# input-breakout.net
KiCad netlist of a schematic drawn in EAGLE
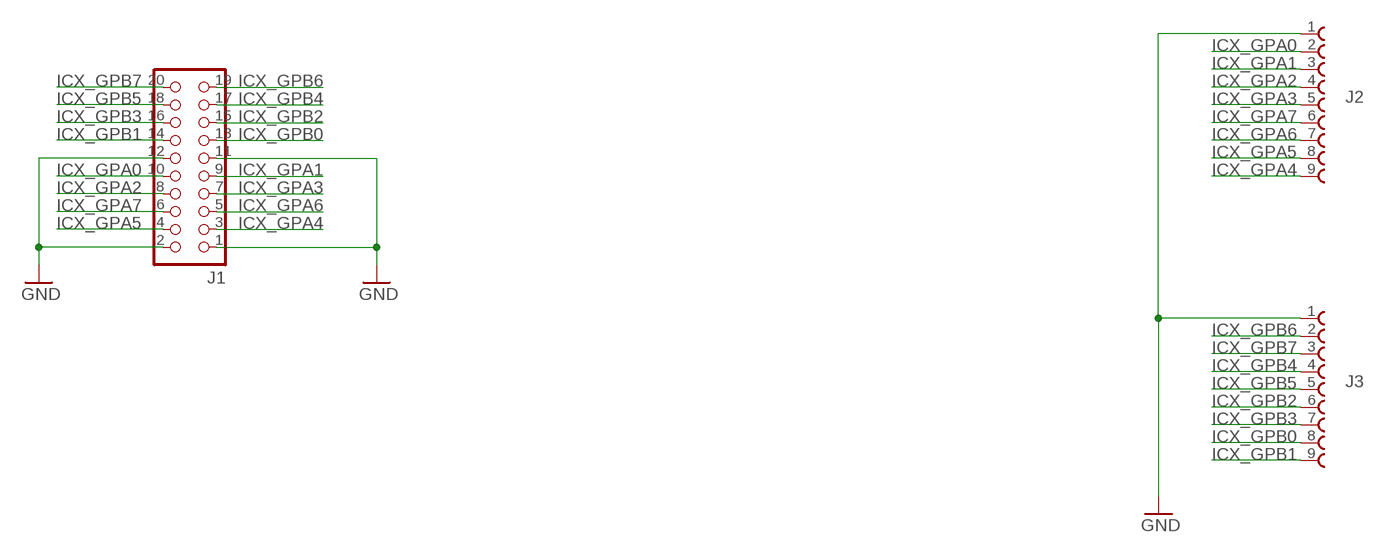
[diagram p0: schematic, sheet 1]

(export (version "E")
  (design (tool "Eeschema 10.0.6"))
  (components
    (comp (ref "J1")
      (value "CON_HEADER_2X10-SHROUDED")
      (footprint "eagle-import:PINSHRD_PTH_2X10")
      (libsource (lib "eagle-import") (part "CON_HEADER_2X10-SHROUDED"))
    )
    (comp (ref "J2")
      (value "69132211000_XX")
      (footprint "eagle-import:69132211000_XX")
      (libsource (lib "eagle-import") (part "69132211000_XX"))
    )
    (comp (ref "J3")
      (value "69132211000_XX")
      (footprint "eagle-import:69132211000_XX")
      (libsource (lib "eagle-import") (part "69132211000_XX"))
    )
  )
  (nets
    (net (code "1") (name "/ICX_GPA0") (class "Default")
      (node (ref "J1") (pin "10") (pinfunction "10_10") (pintype "passive"))
      (node (ref "J2") (pin "2") (pinfunction "2_2") (pintype "passive"))
    )
    (net (code "2") (name "/ICX_GPA1") (class "Default")
      (node (ref "J1") (pin "9") (pinfunction "9_9") (pintype "passive"))
      (node (ref "J2") (pin "3") (pinfunction "3_3") (pintype "passive"))
    )
    (net (code "3") (name "/ICX_GPA2") (class "Default")
      (node (ref "J1") (pin "8") (pinfunction "8_8") (pintype "passive"))
      (node (ref "J2") (pin "4") (pinfunction "4_4") (pintype "passive"))
    )
    (net (code "4") (name "/ICX_GPA3") (class "Default")
      (node (ref "J1") (pin "7") (pinfunction "7_7") (pintype "passive"))
      (node (ref "J2") (pin "5") (pinfunction "5_5") (pintype "passive"))
    )
    (net (code "5") (name "/ICX_GPA4") (class "Default")
      (node (ref "J1") (pin "3") (pinfunction "3_3") (pintype "passive"))
      (node (ref "J2") (pin "9") (pinfunction "9_9") (pintype "passive"))
    )
    (net (code "6") (name "/ICX_GPA5") (class "Default")
      (node (ref "J1") (pin "4") (pinfunction "4_4") (pintype "passive"))
      (node (ref "J2") (pin "8") (pinfunction "8_8") (pintype "passive"))
    )
    (net (code "7") (name "/ICX_GPA6") (class "Default")
      (node (ref "J1") (pin "5") (pinfunction "5_5") (pintype "passive"))
      (node (ref "J2") (pin "7") (pinfunction "7_7") (pintype "passive"))
    )
    (net (code "8") (name "/ICX_GPA7") (class "Default")
      (node (ref "J1") (pin "6") (pinfunction "6_6") (pintype "passive"))
      (node (ref "J2") (pin "6") (pinfunction "6_6") (pintype "passive"))
    )
    (net (code "9") (name "/ICX_GPB0") (class "Default")
      (node (ref "J1") (pin "13") (pinfunction "13_13") (pintype "passive"))
      (node (ref "J3") (pin "8") (pinfunction "8_8") (pintype "passive"))
    )
    (net (code "10") (name "/ICX_GPB1") (class "Default")
      (node (ref "J1") (pin "14") (pinfunction "14_14") (pintype "passive"))
      (node (ref "J3") (pin "9") (pinfunction "9_9") (pintype "passive"))
    )
    (net (code "11") (name "/ICX_GPB2") (class "Default")
      (node (ref "J1") (pin "15") (pinfunction "15_15") (pintype "passive"))
      (node (ref "J3") (pin "6") (pinfunction "6_6") (pintype "passive"))
    )
    (net (code "12") (name "/ICX_GPB3") (class "Default")
      (node (ref "J1") (pin "16") (pinfunction "16_16") (pintype "passive"))
      (node (ref "J3") (pin "7") (pinfunction "7_7") (pintype "passive"))
    )
    (net (code "13") (name "/ICX_GPB4") (class "Default")
      (node (ref "J1") (pin "17") (pinfunction "17_17") (pintype "passive"))
      (node (ref "J3") (pin "4") (pinfunction "4_4") (pintype "passive"))
    )
    (net (code "14") (name "/ICX_GPB5") (class "Default")
      (node (ref "J1") (pin "18") (pinfunction "18_18") (pintype "passive"))
      (node (ref "J3") (pin "5") (pinfunction "5_5") (pintype "passive"))
    )
    (net (code "15") (name "/ICX_GPB6") (class "Default")
      (node (ref "J1") (pin "19") (pinfunction "19_19") (pintype "passive"))
      (node (ref "J3") (pin "2") (pinfunction "2_2") (pintype "passive"))
    )
    (net (code "16") (name "/ICX_GPB7") (class "Default")
      (node (ref "J1") (pin "20") (pinfunction "20_20") (pintype "passive"))
      (node (ref "J3") (pin "3") (pinfunction "3_3") (pintype "passive"))
    )
    (net (code "17") (name "GND") (class "Default")
      (node (ref "J1") (pin "1") (pinfunction "1_1") (pintype "passive"))
      (node (ref "J1") (pin "11") (pinfunction "11_11") (pintype "passive"))
      (node (ref "J1") (pin "12") (pinfunction "12_12") (pintype "passive"))
      (node (ref "J1") (pin "2") (pinfunction "2_2") (pintype "passive"))
      (node (ref "J2") (pin "1") (pinfunction "1_1") (pintype "passive"))
      (node (ref "J3") (pin "1") (pinfunction "1_1") (pintype "passive"))
    )
  )
)
